# schematic.net
KiCad netlist of a schematic drawn in EasyEDA
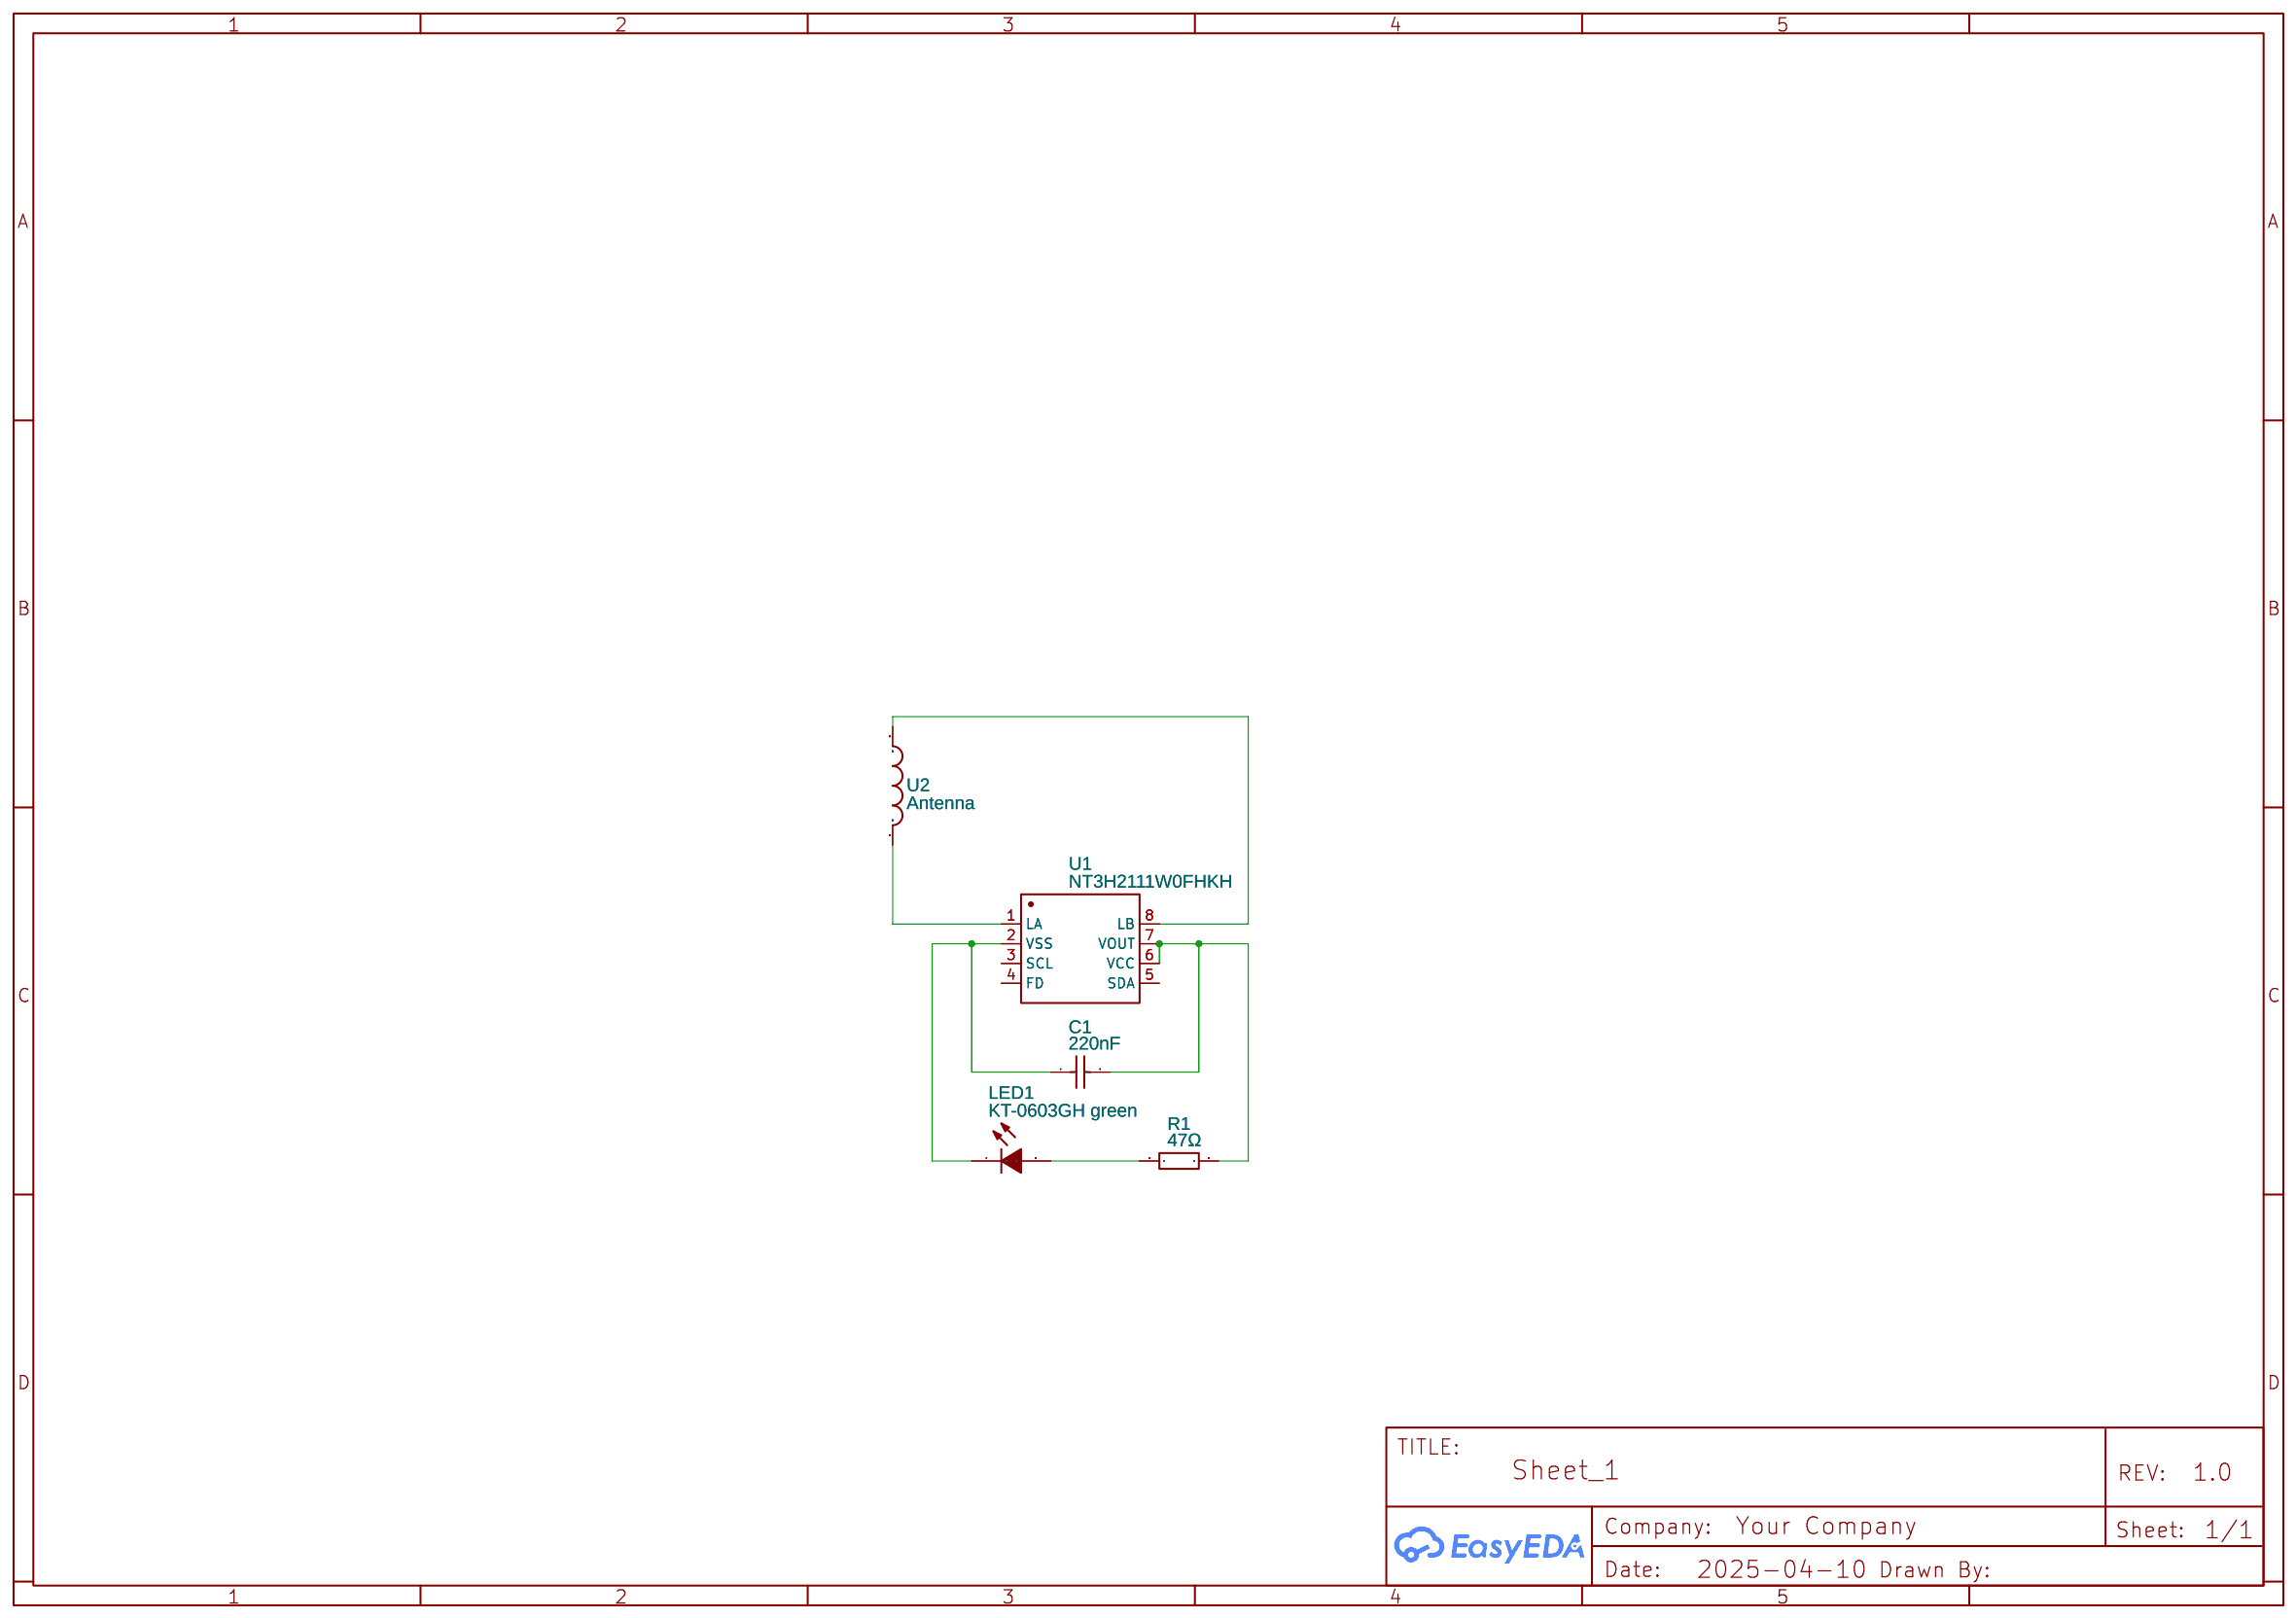
[diagram p0: schematic sheet]

(export (version "E")
  (design (tool "Eeschema 10.0.6"))
  (components
    (comp (ref "C1")
      (value "220nF")
      (fields
        (field (name "Manufacturer Part") "CL10B224KA8NNNC")
        (field (name "Manufacturer") "SAMSUNG(三星)")
      )
      (libsource (lib "") (part "CL10B224KA8NNNC"))
    )
    (comp (ref "LED1")
      (value "KT-0603GH green")
      (fields (field (name "Manufacturer Part") "KT-0603GH"))
      (libsource (lib "") (part "KT-0603GH"))
    )
    (comp (ref "R1")
      (value "47Ω")
      (fields
        (field (name "Manufacturer Part") "0603WAF470JT5E")
        (field (name "Manufacturer") "UNI-ROYAL(厚声)")
      )
      (libsource (lib "") (part "0603WAF470JT5E"))
    )
    (comp (ref "U1")
      (value "NT3H2111W0FHKH")
      (fields (field (name "Manufacturer") "NXP(恩智浦)"))
      (libsource (lib "") (part "NT3H2111W0FHKH"))
    )
    (comp (ref "U2") (value "Antenna") (libsource (lib "") (part "Antenna")))
  )
  (nets
    (net (code "1") (name "Net-(LED1-A)") (class "Default")
      (node (ref "LED1") (pin "2") (pinfunction "A_2") (pintype "input"))
      (node (ref "R1") (pin "1") (pinfunction "1_1") (pintype "input"))
    )
    (net (code "2") (name "Net-(LED1-C)") (class "Default")
      (node (ref "C1") (pin "1") (pinfunction "1_1") (pintype "input"))
      (node (ref "LED1") (pin "1") (pinfunction "C_1") (pintype "input"))
      (node (ref "U1") (pin "2") (pinfunction "VSS_2") (pintype "unspecified"))
    )
    (net (code "3") (name "Net-(U1-LA)") (class "Default")
      (node (ref "U1") (pin "1") (pinfunction "LA_1") (pintype "unspecified"))
      (node (ref "U2") (pin "P$1") (pinfunction "P$1_P$1") (pintype "unspecified"))
    )
    (net (code "4") (name "Net-(U1-LB)") (class "Default")
      (node (ref "U1") (pin "8") (pinfunction "LB_8") (pintype "unspecified"))
      (node (ref "U2") (pin "P$2") (pinfunction "P$2_P$2") (pintype "unspecified"))
    )
    (net (code "5") (name "Net-(U1-VCC)") (class "Default")
      (node (ref "C1") (pin "2") (pinfunction "2_2") (pintype "input"))
      (node (ref "R1") (pin "2") (pinfunction "2_2") (pintype "input"))
      (node (ref "U1") (pin "6") (pinfunction "VCC_6") (pintype "unspecified"))
      (node (ref "U1") (pin "7") (pinfunction "VOUT_7") (pintype "unspecified"))
    )
    (net (code "6") (name "unconnected-(U1-FD-Pad4)") (class "Default")
      (node (ref "U1") (pin "4") (pinfunction "FD_4") (pintype "unspecified"))
    )
    (net (code "7") (name "unconnected-(U1-SCL-Pad3)") (class "Default")
      (node (ref "U1") (pin "3") (pinfunction "SCL_3") (pintype "unspecified"))
    )
    (net (code "8") (name "unconnected-(U1-SDA-Pad5)") (class "Default")
      (node (ref "U1") (pin "5") (pinfunction "SDA_5") (pintype "unspecified"))
    )
  )
)
